# Power_Supply.net
KiCad netlist of a schematic drawn in Altium Designer
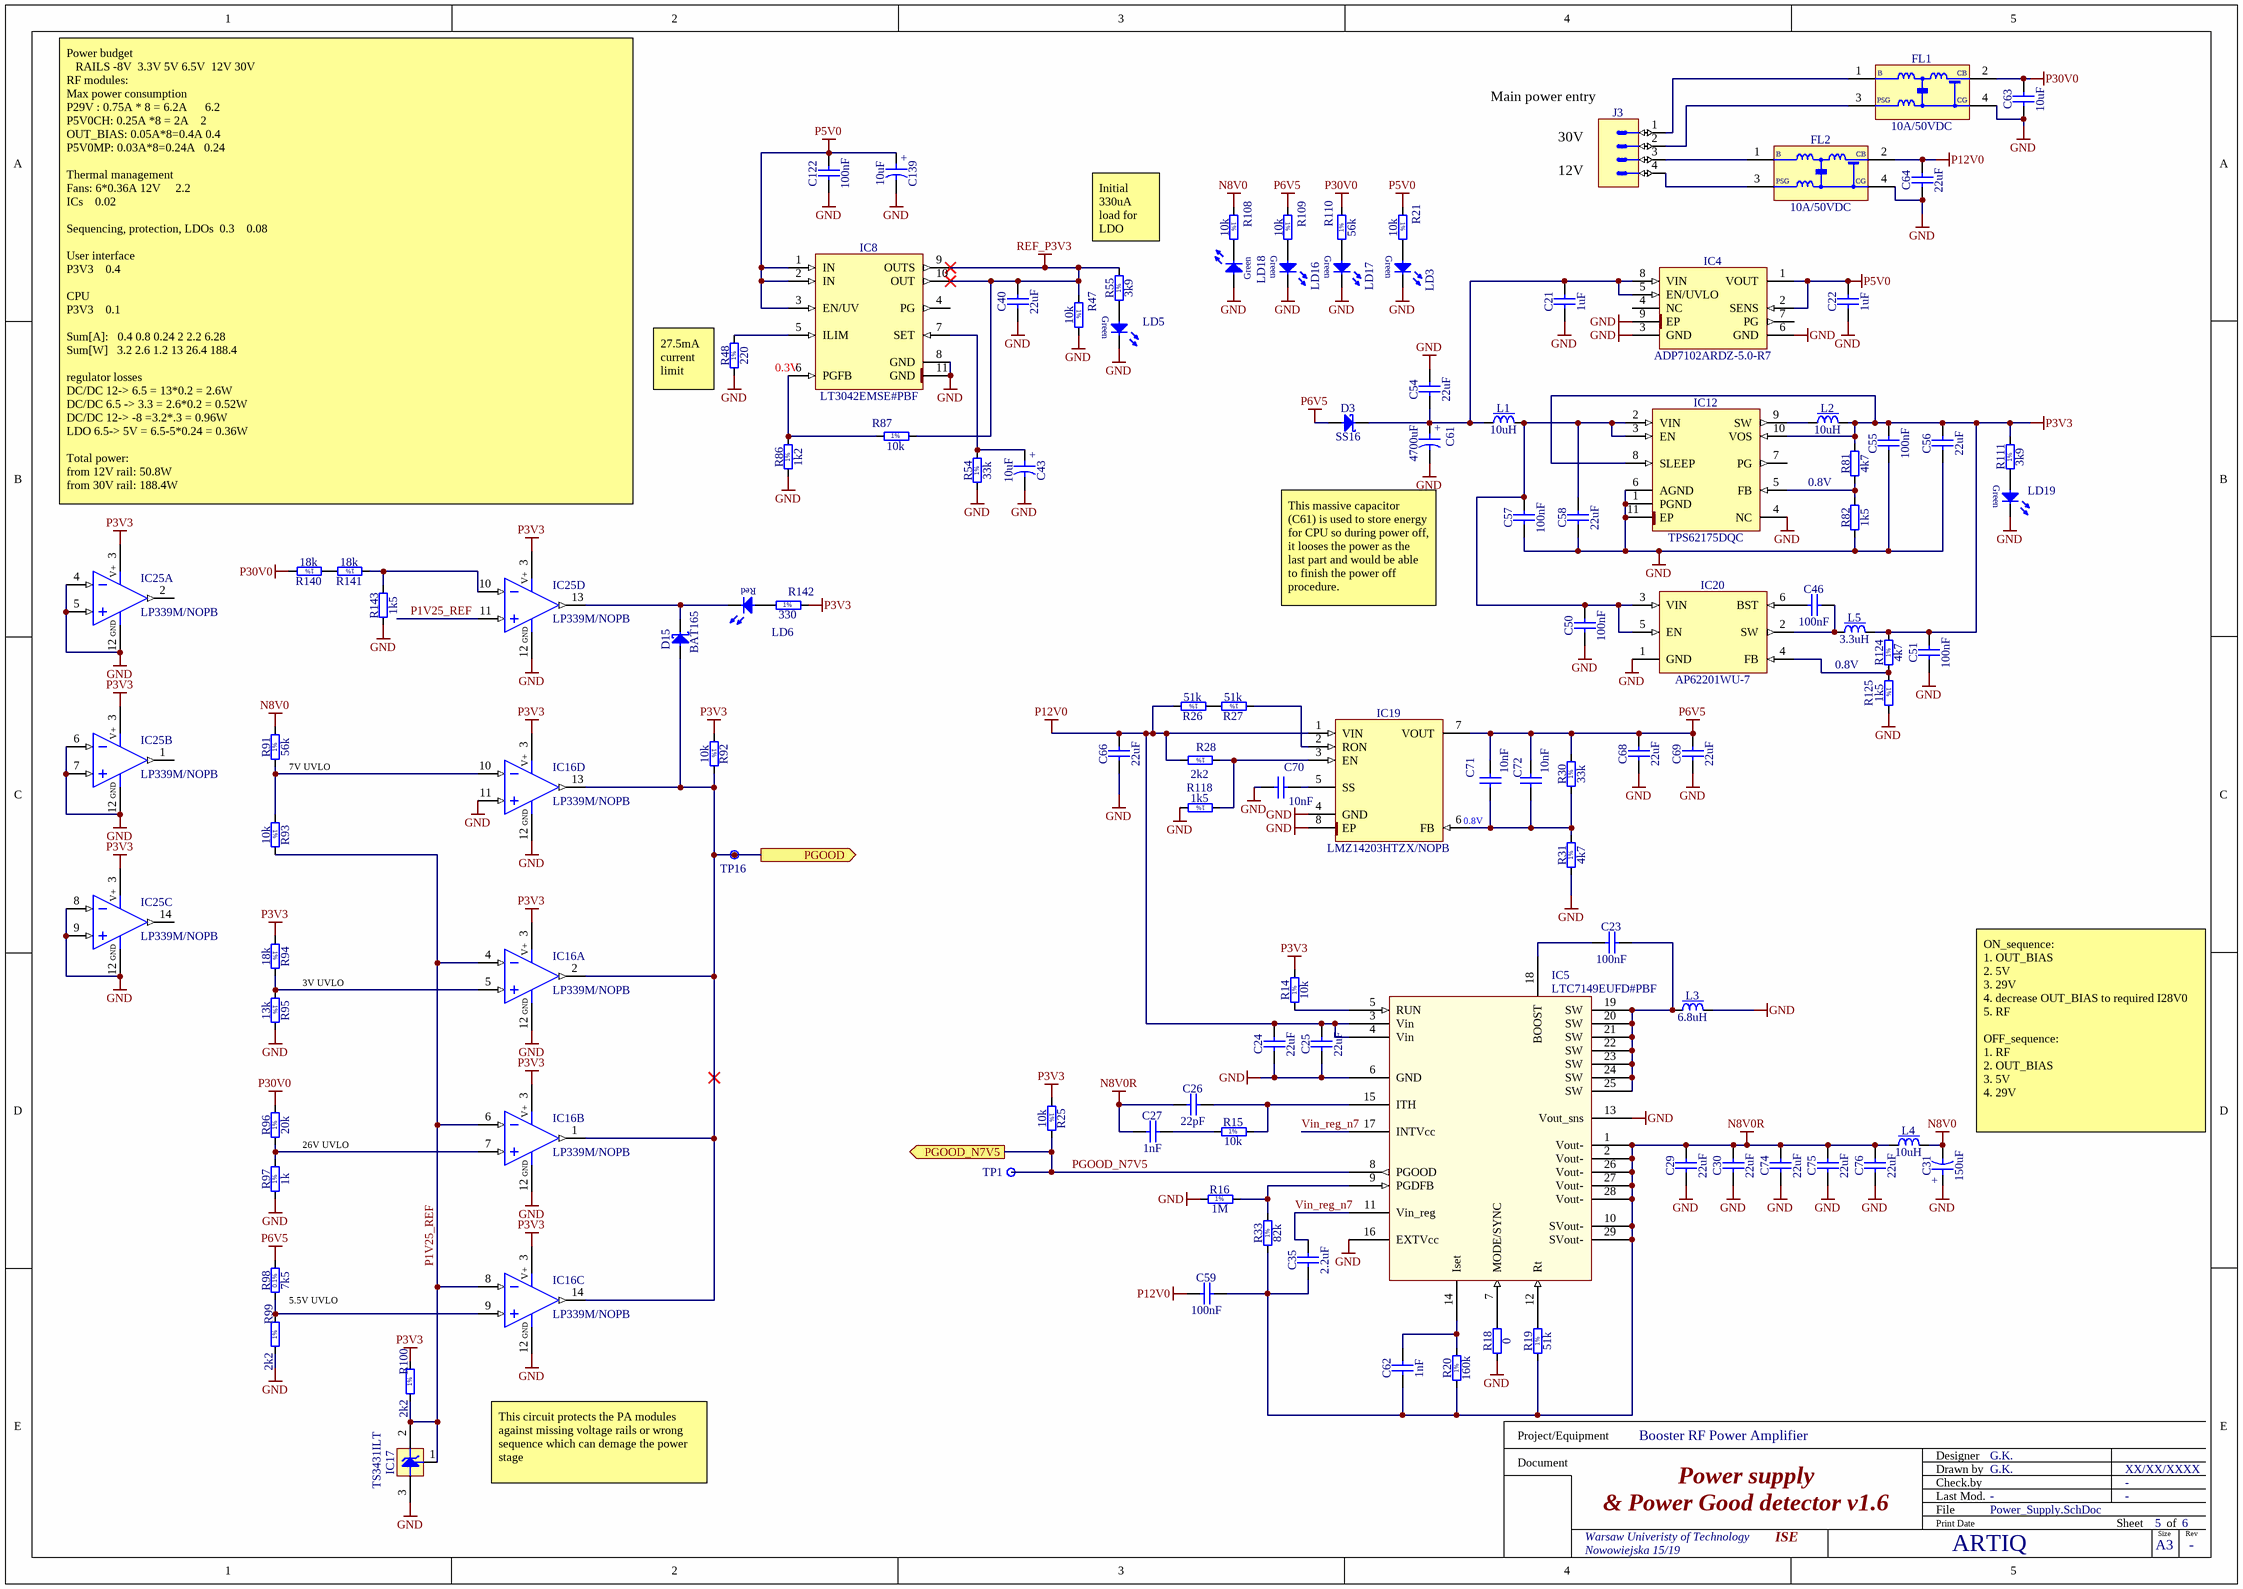
[diagram p0: Power_Supply.SchDoc]

(export (version "E")
  (design (tool "Eeschema 10.0.6"))
  (components
    (comp (ref "C21")
      (value "1uF")
      (footprint "CAPC2012X110N")
      (description "Non-polarised capacitor")
      (fields
        (field (name "PART NUMBER") "CC0805_1UF_50V_10%_X7R")
        (field (name "VOLTAGE") "50V")
        (field (name "AUTHOR") "CERN DEM JLC")
      )
      (libsource (lib "Capacitors") (part "Capacitor - non polarized"))
    )
    (comp (ref "C22")
      (value "1uF")
      (footprint "CAPC2012X110N")
      (description "Non-polarised capacitor")
      (fields
        (field (name "PART NUMBER") "CC0805_1UF_50V_10%_X7R")
        (field (name "VOLTAGE") "50V")
        (field (name "AUTHOR") "CERN DEM JLC")
      )
      (libsource (lib "Capacitors") (part "Capacitor - non polarized"))
    )
    (comp (ref "C23")
      (value "100nF")
      (footprint "CAPC1005X55N")
      (description "Non-polarised capacitor")
      (fields
        (field (name "PART NUMBER") "CC0402_100NF_50V_10%_X7R")
        (field (name "VOLTAGE") "50V")
        (field (name "AUTHOR") "CERN DEM MR")
      )
      (libsource (lib "Capacitors") (part "Capacitor - non polarized"))
    )
    (comp (ref "C24")
      (value "22uF")
      (footprint "CAPC2012X135N")
      (description "Non-polarised capacitor")
      (fields
        (field (name "PART NUMBER") "CC0805_22UF_16V_10%_X5R")
        (field (name "VOLTAGE") "16V")
        (field (name "AUTHOR") "CERN DEM JLC")
      )
      (libsource (lib "Capacitors") (part "Capacitor - non polarized"))
    )
    (comp (ref "C25")
      (value "22uF")
      (footprint "CAPC2012X135N")
      (description "Non-polarised capacitor")
      (fields
        (field (name "PART NUMBER") "CC0805_22UF_16V_10%_X5R")
        (field (name "VOLTAGE") "16V")
        (field (name "AUTHOR") "CERN DEM JLC")
      )
      (libsource (lib "Capacitors") (part "Capacitor - non polarized"))
    )
    (comp (ref "C26")
      (value "22pF")
      (footprint "CAPC1005X55N")
      (description "Non-polarised capacitor")
      (fields
        (field (name "PART NUMBER") "CC0402_22PF_50V_5%_C0G")
        (field (name "VOLTAGE") "50V")
        (field (name "AUTHOR") "CERN DEM JLC")
      )
      (libsource (lib "Capacitors") (part "Capacitor - non polarized"))
    )
    (comp (ref "C27")
      (value "1nF")
      (footprint "CAPC1608X87N")
      (description "Non-polarised capacitor")
      (fields
        (field (name "PART NUMBER") "CC0603_1NF_50V_10%_X7R")
        (field (name "VOLTAGE") "50V")
        (field (name "AUTHOR") "CERN DEM JLC")
      )
      (libsource (lib "Capacitors") (part "Capacitor - non polarized"))
    )
    (comp (ref "C29")
      (value "22uF")
      (footprint "CAPC2012X135N")
      (description "Non-polarised capacitor")
      (fields
        (field (name "PART NUMBER") "CC0805_22UF_16V_10%_X5R")
        (field (name "VOLTAGE") "16V")
        (field (name "AUTHOR") "CERN DEM JLC")
      )
      (libsource (lib "Capacitors") (part "Capacitor - non polarized"))
    )
    (comp (ref "C30")
      (value "22uF")
      (footprint "CAPC2012X135N")
      (description "Non-polarised capacitor")
      (fields
        (field (name "PART NUMBER") "CC0805_22UF_16V_10%_X5R")
        (field (name "VOLTAGE") "16V")
        (field (name "AUTHOR") "CERN DEM JLC")
      )
      (libsource (lib "Capacitors") (part "Capacitor - non polarized"))
    )
    (comp (ref "C31")
      (value "150uF")
      (footprint "CAPMP7343X310N")
      (description "Polarised capacitor")
      (fields
        (field (name "PART NUMBER") "CTE7343-31_150UF_16V_10%_LESR0100")
        (field (name "VOLTAGE") "16V")
        (field (name "AUTHOR") "CERN DEM JLC")
      )
      (libsource (lib "Capacitors") (part "Capacitor - polarized"))
    )
    (comp (ref "C35")
      (value "2.2uF")
      (footprint "CAPC1608X90N")
      (description "Non-polarised capacitor")
      (fields
        (field (name "PART NUMBER") "CC0603_2.2UF_10V_20%_X7R")
        (field (name "VOLTAGE") "10V")
        (field (name "AUTHOR") "CERN DEM JLC")
      )
      (libsource (lib "Capacitors") (part "Capacitor - non polarized"))
    )
    (comp (ref "C40")
      (value "22uF")
      (footprint "CAPC2012X135N")
      (description "Non-polarised capacitor")
      (fields
        (field (name "PART NUMBER") "CC0805_22UF_16V_10%_X5R")
        (field (name "VOLTAGE") "16V")
        (field (name "AUTHOR") "CERN DEM JLC")
      )
      (libsource (lib "Capacitors") (part "Capacitor - non polarized"))
    )
    (comp (ref "C43")
      (value "10uF")
      (footprint "CAPAE430X540N")
      (description "Polarised capacitor")
      (fields
        (field (name "PART NUMBER") "CAE430-540_10UF_16V_20%")
        (field (name "VOLTAGE") "16V")
        (field (name "AUTHOR") "CERN DEM JLC")
      )
      (libsource (lib "Capacitors") (part "Capacitor - polarized"))
    )
    (comp (ref "C46")
      (value "100nF")
      (footprint "CAPC1005X55N")
      (description "Non-polarised capacitor")
      (fields
        (field (name "PART NUMBER") "CC0402_100NF_16V_10%_X7R")
        (field (name "VOLTAGE") "16V")
        (field (name "AUTHOR") "CERN DEM JLC")
      )
      (libsource (lib "Capacitors") (part "Capacitor - non polarized"))
    )
    (comp (ref "C50")
      (value "100nF")
      (footprint "CAPC1005X55N")
      (description "Non-polarised capacitor")
      (fields
        (field (name "PART NUMBER") "CC0402_100NF_16V_10%_X7R")
        (field (name "VOLTAGE") "16V")
        (field (name "AUTHOR") "CERN DEM JLC")
      )
      (libsource (lib "Capacitors") (part "Capacitor - non polarized"))
    )
    (comp (ref "C51")
      (value "100nF")
      (footprint "CAPC1005X55N")
      (description "Non-polarised capacitor")
      (fields
        (field (name "PART NUMBER") "CC0402_100NF_16V_10%_X5R")
        (field (name "VOLTAGE") "16V")
        (field (name "AUTHOR") "CERN DEM JLC")
      )
      (libsource (lib "Capacitors") (part "Capacitor - non polarized"))
    )
    (comp (ref "C54")
      (value "22uF")
      (footprint "CAPC2012X135N")
      (description "Non-polarised capacitor")
      (fields
        (field (name "PART NUMBER") "CC0805_22UF_16V_10%_X5R")
        (field (name "VOLTAGE") "16V")
        (field (name "AUTHOR") "CERN DEM JLC")
      )
      (libsource (lib "Capacitors") (part "Capacitor - non polarized"))
    )
    (comp (ref "C55")
      (value "100nF")
      (footprint "CAPC1005X55N")
      (description "Non-polarised capacitor")
      (fields
        (field (name "PART NUMBER") "CC0402_100NF_16V_10%_X7R")
        (field (name "VOLTAGE") "16V")
        (field (name "AUTHOR") "CERN DEM JLC")
      )
      (libsource (lib "Capacitors") (part "Capacitor - non polarized"))
    )
    (comp (ref "C56")
      (value "22uF")
      (footprint "CAPC2012X135N")
      (description "Non-polarised capacitor")
      (fields
        (field (name "PART NUMBER") "CC0805_22UF_16V_10%_X5R")
        (field (name "VOLTAGE") "16V")
        (field (name "AUTHOR") "CERN DEM JLC")
      )
      (libsource (lib "Capacitors") (part "Capacitor - non polarized"))
    )
    (comp (ref "C57")
      (value "100nF")
      (footprint "CAPC1005X55N")
      (description "Non-polarised capacitor")
      (fields
        (field (name "PART NUMBER") "CC0402_100NF_16V_10%_X7R")
        (field (name "VOLTAGE") "16V")
        (field (name "AUTHOR") "CERN DEM JLC")
      )
      (libsource (lib "Capacitors") (part "Capacitor - non polarized"))
    )
    (comp (ref "C58")
      (value "22uF")
      (footprint "CAPC2012X135N")
      (description "Non-polarised capacitor")
      (fields
        (field (name "PART NUMBER") "CC0805_22UF_16V_10%_X5R")
        (field (name "VOLTAGE") "16V")
        (field (name "AUTHOR") "CERN DEM JLC")
      )
      (libsource (lib "Capacitors") (part "Capacitor - non polarized"))
    )
    (comp (ref "C59")
      (value "100nF")
      (footprint "CAPC1005X55N")
      (description "Non-polarised capacitor")
      (fields
        (field (name "PART NUMBER") "CC0402_100NF_50V_10%_X7R")
        (field (name "VOLTAGE") "50V")
        (field (name "AUTHOR") "CERN DEM MR")
      )
      (libsource (lib "Capacitors") (part "Capacitor - non polarized"))
    )
    (comp (ref "C61")
      (value "4700uF")
      (footprint "CAPAE1900X1680N")
      (description "Polarised capacitor")
      (fields
        (field (name "PART NUMBER") "CAE1900-1680_4700UF_16V_20%")
        (field (name "VOLTAGE") "16V")
        (field (name "AUTHOR") "CERN DEM JLC")
      )
      (libsource (lib "Capacitors") (part "Capacitor - polarized"))
    )
    (comp (ref "C62")
      (value "1nF")
      (footprint "CAPC1608X87N")
      (description "Non-polarised capacitor")
      (fields
        (field (name "PART NUMBER") "CC0603_1NF_50V_10%_X7R")
        (field (name "VOLTAGE") "50V")
        (field (name "AUTHOR") "CERN DEM JLC")
      )
      (libsource (lib "Capacitors") (part "Capacitor - non polarized"))
    )
    (comp (ref "C63")
      (value "10uF")
      (footprint "CAPC3216X190N")
      (description "Non-polarised capacitor")
      (fields
        (field (name "PART NUMBER") "CC1206_10UF_50V_10%_X5R_TDK_CGA5L3X5R1H106K160AB")
        (field (name "VOLTAGE") "50V")
        (field (name "AUTHOR") "CERN DEM BC")
      )
      (libsource (lib "Capacitors") (part "Capacitor - non polarized"))
    )
    (comp (ref "C64")
      (value "22uF")
      (footprint "CAPC2012X135N")
      (description "Non-polarised capacitor")
      (fields
        (field (name "PART NUMBER") "CC0805_22UF_16V_10%_X5R")
        (field (name "VOLTAGE") "16V")
        (field (name "AUTHOR") "CERN DEM JLC")
      )
      (libsource (lib "Capacitors") (part "Capacitor - non polarized"))
    )
    (comp (ref "C66")
      (value "22uF")
      (footprint "CAPC2012X135N")
      (description "Non-polarised capacitor")
      (fields
        (field (name "PART NUMBER") "CC0805_22UF_16V_10%_X5R")
        (field (name "VOLTAGE") "16V")
        (field (name "AUTHOR") "CERN DEM JLC")
      )
      (libsource (lib "Capacitors") (part "Capacitor - non polarized"))
    )
    (comp (ref "C68")
      (value "22uF")
      (footprint "CAPC2012X135N")
      (description "Non-polarised capacitor")
      (fields
        (field (name "PART NUMBER") "CC0805_22UF_16V_10%_X5R")
        (field (name "VOLTAGE") "16V")
        (field (name "AUTHOR") "CERN DEM JLC")
      )
      (libsource (lib "Capacitors") (part "Capacitor - non polarized"))
    )
    (comp (ref "C69")
      (value "22uF")
      (footprint "CAPC2012X135N")
      (description "Non-polarised capacitor")
      (fields
        (field (name "PART NUMBER") "CC0805_22UF_16V_10%_X5R")
        (field (name "VOLTAGE") "16V")
        (field (name "AUTHOR") "CERN DEM JLC")
      )
      (libsource (lib "Capacitors") (part "Capacitor - non polarized"))
    )
    (comp (ref "C70")
      (value "10nF")
      (footprint "CAPC1608X87N")
      (description "Non-polarised capacitor")
      (fields
        (field (name "PART NUMBER") "CC0603_10NF_50V_5%_C0G")
        (field (name "VOLTAGE") "50V")
        (field (name "AUTHOR") "CERN DEM JLC")
      )
      (libsource (lib "Capacitors") (part "Capacitor - non polarized"))
    )
    (comp (ref "C71")
      (value "10nF")
      (footprint "CAPC1608X87N")
      (description "Non-polarised capacitor")
      (fields
        (field (name "PART NUMBER") "CC0603_10NF_50V_5%_C0G")
        (field (name "VOLTAGE") "50V")
        (field (name "AUTHOR") "CERN DEM JLC")
      )
      (libsource (lib "Capacitors") (part "Capacitor - non polarized"))
    )
    (comp (ref "C72")
      (value "10nF")
      (footprint "CAPC1608X87N")
      (description "Non-polarised capacitor")
      (fields
        (field (name "PART NUMBER") "CC0603_10NF_50V_5%_C0G")
        (field (name "VOLTAGE") "50V")
        (field (name "AUTHOR") "CERN DEM JLC")
      )
      (libsource (lib "Capacitors") (part "Capacitor - non polarized"))
    )
    (comp (ref "C74")
      (value "22uF")
      (footprint "CAPC2012X135N")
      (description "Non-polarised capacitor")
      (fields
        (field (name "PART NUMBER") "CC0805_22UF_16V_10%_X5R")
        (field (name "VOLTAGE") "16V")
        (field (name "AUTHOR") "CERN DEM JLC")
      )
      (libsource (lib "Capacitors") (part "Capacitor - non polarized"))
    )
    (comp (ref "C75")
      (value "22uF")
      (footprint "CAPC2012X135N")
      (description "Non-polarised capacitor")
      (fields
        (field (name "PART NUMBER") "CC0805_22UF_16V_10%_X5R")
        (field (name "VOLTAGE") "16V")
        (field (name "AUTHOR") "CERN DEM JLC")
      )
      (libsource (lib "Capacitors") (part "Capacitor - non polarized"))
    )
    (comp (ref "C76")
      (value "22uF")
      (footprint "CAPC2012X135N")
      (description "Non-polarised capacitor")
      (fields
        (field (name "PART NUMBER") "CC0805_22UF_16V_10%_X5R")
        (field (name "VOLTAGE") "16V")
        (field (name "AUTHOR") "CERN DEM JLC")
      )
      (libsource (lib "Capacitors") (part "Capacitor - non polarized"))
    )
    (comp (ref "C122")
      (value "100nF")
      (footprint "CAPC1005X55N")
      (description "Non-polarised capacitor")
      (fields
        (field (name "PART NUMBER") "CC0402_100NF_16V_10%_X7R")
        (field (name "VOLTAGE") "16V")
        (field (name "AUTHOR") "CERN DEM JLC")
      )
      (libsource (lib "Capacitors") (part "Capacitor - non polarized"))
    )
    (comp (ref "C139")
      (value "10uF")
      (footprint "CAPAE430X540N")
      (description "Polarised capacitor")
      (fields
        (field (name "PART NUMBER") "CAE430-540_10UF_16V_20%")
        (field (name "VOLTAGE") "16V")
        (field (name "AUTHOR") "CERN DEM JLC")
      )
      (libsource (lib "Capacitors") (part "Capacitor - polarized"))
    )
    (comp (ref "D3")
      (value "SS16")
      (footprint "DIOM5127X229N")
      (description "Schottky Diode")
      (fields
        (field (name "VOLTAGE") "60V")
        (field (name "POWER") "1A")
        (field (name "AUTHOR") "CERN DEM JLC")
      )
      (libsource (lib "ICs And Semiconductors") (part "Diode Schottky"))
    )
    (comp (ref "D15")
      (value "BAT165")
      (footprint "SOD2512X110N")
      (description "Schottky Diode")
      (fields
        (field (name "VOLTAGE") "40V")
        (field (name "POWER") "750mA")
        (field (name "AUTHOR") "CERN DEM JLC")
      )
      (libsource (lib "ICs And Semiconductors") (part "Diode Schottky"))
    )
    (comp (ref "FL1")
      (value "10A/50VDC")
      (footprint "FIL_MURATA_BNX02")
      (description "Block Type EMIFIL (LC Combined)")
      (fields
        (field (name "PART NUMBER") "FIL_MURATA_BNX022-01L")
        (field (name "MANUFACTURER") "MURATA")
        (field (name "AUTHOR") "CERN DEM JLC")
      )
      (libsource (lib "Inductors & Transformers") (part "FIL_MURATA_BNX02"))
    )
    (comp (ref "FL2")
      (value "10A/50VDC")
      (footprint "FIL_MURATA_BNX02")
      (description "Block Type EMIFIL (LC Combined)")
      (fields
        (field (name "PART NUMBER") "FIL_MURATA_BNX022-01L")
        (field (name "MANUFACTURER") "MURATA")
        (field (name "AUTHOR") "CERN DEM JLC")
      )
      (libsource (lib "Inductors & Transformers") (part "FIL_MURATA_BNX02"))
    )
    (comp (ref "IC4")
      (value "ADP7102ARDZ-5.0-R7")
      (footprint "SOIC127P600X175-9N-R241X309")
      (description "300 mA, Low Noise, CMOS LDO Linear Regulator")
      (fields (field (name "MANUFACTURER") "ANALOG DEVICES") (field (name "AUTHOR") "CERN DEM JLC"))
      (libsource (lib "ICs And Semiconductors") (part "ADP7102ARDZ-X.X-R7"))
    )
    (comp (ref "IC5")
      (value "LTC7149EUFD#PBF")
      (footprint "QFN50P400X500X80_HS-29N")
      (description "LTC7149 - 60V, 4A Synchronous Step-Down Regulator for Inverting Outputs")
      (fields (field (name "MANUFACTURER") "Linear technology"))
      (libsource (lib "misc") (part "LTC7149EUFD#PBF"))
    )
    (comp (ref "IC8")
      (value "LT3042EMSE#PBF")
      (footprint "SOP50P490X110-11N-R168X198")
      (description "20V, 200mA, Ultralow Noise, Ultrahigh PSRR RF Linear Regulator")
      (fields (field (name "MANUFACTURER") "LINEAR TECHNOLOGY") (field (name "AUTHOR") "CERN DEM MR"))
      (libsource (lib "ICs And Semiconductors") (part "LT3042"))
    )
    (comp (ref "IC12")
      (value "TPS62175DQC")
      (footprint "SON50P200X300X80-11N-R94X250")
      (description "4.75-28VDC to 1-6VDC, 500mA Step-Down Converter With Sleep Mode")
      (fields (field (name "MANUFACTURER") "TEXAS INSTRUMENTS") (field (name "AUTHOR") "CERN DEM JMW"))
      (libsource (lib "ICs And Semiconductors") (part "TPS62175"))
    )
    (comp (ref "IC16")
      (value "LP339M/NOPB")
      (footprint "SOIC127P600X175-14N")
      (description "Quad Operational Amplifier")
      (fields (field (name "MANUFACTURER") "TEXAS INSTRUMENTS") (field (name "AUTHOR") "CERN DEM MR"))
      (libsource (lib "ICs And Semiconductors") (part "Operational Amplifier x4 Type5"))
    )
    (comp (ref "IC17")
      (value "TS3431ILT")
      (footprint "SOT95P237X112-3N")
      (description "Precision Reference 1=Adj 2=Cathode 3=Anode")
      (fields (field (name "MANUFACTURER") "ST MICROELECTRONICS") (field (name "AUTHOR") "CERN DEM JLC"))
      (libsource (lib "ICs And Semiconductors") (part "VREF 1ADJ-2C-3A"))
    )
    (comp (ref "IC19")
      (value "LMZ14203HTZX/NOPB")
      (footprint "TEXAS_TO-PMOD (NDW)")
      (description "3A SIMPLE SWITCHER® Power Module with 42V Maximum Input Voltage")
      (fields (field (name "MANUFACTURER") "TEXAS INSTRUMENTS") (field (name "AUTHOR") "GK"))
      (libsource (lib "LIBRARY_SCH") (part "PM_LMZ14203"))
    )
    (comp (ref "IC20")
      (value "AP62201WU-7")
      (footprint "SOT95P280X100-6N")
      (description "4.2V TO 18V INPUT, 2A LOW IQ SYNCHRONOUS BUCK CONVERTER")
      (fields (field (name "MANUFACTURER") "DIODES INCORPORATED") (field (name "AUTHOR") "CERN DEM HF"))
      (libsource (lib "ICs And Semiconductors") (part "AP62201WU"))
    )
    (comp (ref "IC25")
      (value "LP339M/NOPB")
      (footprint "SOIC127P600X175-14N")
      (description "Quad Operational Amplifier")
      (fields (field (name "MANUFACTURER") "TEXAS INSTRUMENTS") (field (name "AUTHOR") "CERN DEM MR"))
      (libsource (lib "ICs And Semiconductors") (part "Operational Amplifier x4 Type5"))
    )
    (comp (ref "J3")
      (value "~")
      (footprint "PHOENIX_1755752")
      (description "Connector 4 Male")
      (fields
        (field (name "PART NUMBER") "PHOENIX_1755752")
        (field (name "MANUFACTURER") "PHOENIX CONTACT")
        (field (name "AUTHOR") "CERN DEM JLC")
      )
      (libsource (lib "Connectors") (part "Connector 4 Male"))
    )
    (comp (ref "L1")
      (value "10uH")
      (footprint "IND_MURATA-PS_8400")
      (description "Inductor With Core")
      (fields
        (field (name "PART NUMBER") "IND_10UH_10%_MURATA-PS_8400")
        (field (name "POWER") "950mA")
        (field (name "AUTHOR") "CERN DEM JLC")
      )
      (libsource (lib "Inductors & Transformers") (part "Inductor With Magnetic core"))
    )
    (comp (ref "L2")
      (value "10uH")
      (footprint "IND_MURATA-PS_8400")
      (description "Inductor With Core")
      (fields
        (field (name "PART NUMBER") "IND_10UH_10%_MURATA-PS_8400")
        (field (name "POWER") "950mA")
        (field (name "AUTHOR") "CERN DEM JLC")
      )
      (libsource (lib "Inductors & Transformers") (part "Inductor With Magnetic core"))
    )
    (comp (ref "L3")
      (value "6.8uH")
      (footprint "INDM6965X300N")
      (description "Inductor With Core")
      (fields
        (field (name "PART NUMBER") "IND2525_6.8UH_20%_VISHAY_IHLP-2525CZ")
        (field (name "POWER") "9A")
        (field (name "AUTHOR") "CERN DEM JLC")
      )
      (libsource (lib "Inductors & Transformers") (part "Inductor With Magnetic core"))
    )
    (comp (ref "L4")
      (value "10uH")
      (footprint "IND_MURATA-PS_8400")
      (description "Inductor With Core")
      (fields
        (field (name "PART NUMBER") "IND_10UH_10%_MURATA-PS_8400")
        (field (name "POWER") "950mA")
        (field (name "AUTHOR") "CERN DEM JLC")
      )
      (libsource (lib "Inductors & Transformers") (part "Inductor With Magnetic core"))
    )
    (comp (ref "L5")
      (value "3.3uH")
      (footprint "IND_WURTH_WE-TPC_4828")
      (description "Inductor With Core")
      (fields
        (field (name "PART NUMBER") "IND_3.3UH_30%_WURTH_WE-TPC_744043003")
        (field (name "POWER") "2.15A")
        (field (name "AUTHOR") "CERN DEM JLC")
      )
      (libsource (lib "Inductors & Transformers") (part "Inductor With Magnetic core"))
    )
    (comp (ref "LD3")
      (value "Green")
      (footprint "LED_KINGBRIGHT_KPH-1608CGCK")
      (description "LED Green 1C 2A")
      (fields
        (field (name "PART NUMBER") "LED_KINGBRIGHT_KPH-1608CGCK")
        (field (name "MANUFACTURER") "KINGBRIGHT")
        (field (name "AUTHOR") "CERN DEM JLC")
      )
      (libsource (lib "ICs And Semiconductors") (part "LED Green 1C 2A"))
    )
    (comp (ref "LD5")
      (value "Green")
      (footprint "LED_OSRAM_LGL29K")
      (description "LED Green 1C 2A")
      (fields
        (field (name "PART NUMBER") "LED_OSRAM_LG L29K-G2J1-24-Z")
        (field (name "MANUFACTURER") "OSRAM")
        (field (name "AUTHOR") "CERN DEM JLC")
      )
      (libsource (lib "ICs And Semiconductors") (part "LED Green 1C 2A"))
    )
    (comp (ref "LD6")
      (value "Hyper Red")
      (footprint "LED_KINGBRIGHT_KPH-1608SURCK")
      (description "LED Red 1C 2A")
      (fields
        (field (name "PART NUMBER") "LED_KINGBRIGHT_KPH-1608SURCK")
        (field (name "MANUFACTURER") "KINGBRIGHT")
        (field (name "AUTHOR") "CERN DEM JLC")
      )
      (libsource (lib "ICs And Semiconductors") (part "LED Red 1C 2A"))
    )
    (comp (ref "LD16")
      (value "Green")
      (footprint "LED_KINGBRIGHT_KPH-1608CGCK")
      (description "LED Green 1C 2A")
      (fields
        (field (name "PART NUMBER") "LED_KINGBRIGHT_KPH-1608CGCK")
        (field (name "MANUFACTURER") "KINGBRIGHT")
        (field (name "AUTHOR") "CERN DEM JLC")
      )
      (libsource (lib "ICs And Semiconductors") (part "LED Green 1C 2A"))
    )
    (comp (ref "LD17")
      (value "Green")
      (footprint "LED_KINGBRIGHT_KPH-1608CGCK")
      (description "LED Green 1C 2A")
      (fields
        (field (name "PART NUMBER") "LED_KINGBRIGHT_KPH-1608CGCK")
        (field (name "MANUFACTURER") "KINGBRIGHT")
        (field (name "AUTHOR") "CERN DEM JLC")
      )
      (libsource (lib "ICs And Semiconductors") (part "LED Green 1C 2A"))
    )
    (comp (ref "LD18")
      (value "Green")
      (footprint "LED_KINGBRIGHT_KPH-1608CGCK")
      (description "LED Green 1C 2A")
      (fields
        (field (name "PART NUMBER") "LED_KINGBRIGHT_KPH-1608CGCK")
        (field (name "MANUFACTURER") "KINGBRIGHT")
        (field (name "AUTHOR") "CERN DEM JLC")
      )
      (libsource (lib "ICs And Semiconductors") (part "LED Green 1C 2A"))
    )
    (comp (ref "LD19")
      (value "Green")
      (footprint "LED_OSRAM_LGL29K")
      (description "LED Green 1C 2A")
      (fields
        (field (name "PART NUMBER") "LED_OSRAM_LG L29K-G2J1-24-Z")
        (field (name "MANUFACTURER") "OSRAM")
        (field (name "AUTHOR") "CERN DEM JLC")
      )
      (libsource (lib "ICs And Semiconductors") (part "LED Green 1C 2A"))
    )
    (comp (ref "R14")
      (value "10k")
      (footprint "RESC1005X40N")
      (description "Resistor - 1%")
      (fields
        (field (name "PART NUMBER") "R0402_10K_1%_0.0625W_100PPM")
        (field (name "POWER") "0.0625W")
        (field (name "AUTHOR") "CERN DEM JLC")
      )
      (libsource (lib "Resistors") (part "Resistor - 1%"))
    )
    (comp (ref "R15")
      (value "10k")
      (footprint "RESC1005X40N")
      (description "Resistor - 1%")
      (fields
        (field (name "PART NUMBER") "R0402_10K_1%_0.0625W_100PPM")
        (field (name "POWER") "0.0625W")
        (field (name "AUTHOR") "CERN DEM JLC")
      )
      (libsource (lib "Resistors") (part "Resistor - 1%"))
    )
    (comp (ref "R16")
      (value "1M")
      (footprint "RESC1005X40N")
      (description "Resistor - 1%")
      (fields
        (field (name "PART NUMBER") "R0402_1M_1%_0.0625W_100PPM")
        (field (name "POWER") "0.0625W")
        (field (name "AUTHOR") "CERN DEM JLC")
      )
      (libsource (lib "Resistors") (part "Resistor - 1%"))
    )
    (comp (ref "R18")
      (value "0")
      (footprint "RESC1005X40N")
      (description "Resistor")
      (fields
        (field (name "PART NUMBER") "R0402_0R_JUMPER")
        (field (name "MANUFACTURER") "GENERIC")
        (field (name "AUTHOR") "CERN DEM JLC")
      )
      (libsource (lib "Resistors") (part "Resistor"))
    )
    (comp (ref "R19")
      (value "51k")
      (footprint "RESC1005X40N")
      (description "Resistor - 1%")
      (fields
        (field (name "PART NUMBER") "R0402_51K_1%_0.0625W_100PPM")
        (field (name "POWER") "0.0625W")
        (field (name "AUTHOR") "CERN DEM JLC")
      )
      (libsource (lib "Resistors") (part "Resistor - 1%"))
    )
    (comp (ref "R20")
      (value "160k")
      (footprint "RESC1005X40N")
      (description "Resistor - 1%")
      (fields
        (field (name "PART NUMBER") "R0402_160K_1%_0.0625W_100PPM")
        (field (name "POWER") "0.0625W")
        (field (name "AUTHOR") "CERN DEM JLC")
      )
      (libsource (lib "Resistors") (part "Resistor - 1%"))
    )
    (comp (ref "R21")
      (value "10k")
      (footprint "RESC1005X40N")
      (description "Resistor - 1%")
      (fields
        (field (name "PART NUMBER") "R0402_10K_1%_0.0625W_100PPM")
        (field (name "POWER") "0.0625W")
        (field (name "AUTHOR") "CERN DEM JLC")
      )
      (libsource (lib "Resistors") (part "Resistor - 1%"))
    )
    (comp (ref "R25")
      (value "10k")
      (footprint "RESC1005X40N")
      (description "Resistor - 1%")
      (fields
        (field (name "PART NUMBER") "R0402_10K_1%_0.0625W_100PPM")
        (field (name "POWER") "0.0625W")
        (field (name "AUTHOR") "CERN DEM JLC")
      )
      (libsource (lib "Resistors") (part "Resistor - 1%"))
    )
    (comp (ref "R26")
      (value "51k")
      (footprint "RESC1005X40N")
      (description "Resistor - 1%")
      (fields
        (field (name "PART NUMBER") "R0402_51K_1%_0.0625W_100PPM")
        (field (name "POWER") "0.0625W")
        (field (name "AUTHOR") "CERN DEM JLC")
      )
      (libsource (lib "Resistors") (part "Resistor - 1%"))
    )
    (comp (ref "R27")
      (value "51k")
      (footprint "RESC1005X40N")
      (description "Resistor - 1%")
      (fields
        (field (name "PART NUMBER") "R0402_51K_1%_0.0625W_100PPM")
        (field (name "POWER") "0.0625W")
        (field (name "AUTHOR") "CERN DEM JLC")
      )
      (libsource (lib "Resistors") (part "Resistor - 1%"))
    )
    (comp (ref "R28")
      (value "2k2")
      (footprint "RESC1005X40N")
      (description "Resistor - 1%")
      (fields
        (field (name "PART NUMBER") "R0402_2K2_1%_0.0625W_100PPM")
        (field (name "POWER") "0.0625W")
        (field (name "AUTHOR") "CERN DEM JLC")
      )
      (libsource (lib "Resistors") (part "Resistor - 1%"))
    )
    (comp (ref "R30")
      (value "33k")
      (footprint "RESC1608X55N")
      (description "Resistor - 1%")
      (fields
        (field (name "PART NUMBER") "R0603_33K_1%_0.1W_100PPM")
        (field (name "POWER") "0.1W")
        (field (name "AUTHOR") "CERN DEM JLC")
      )
      (libsource (lib "Resistors") (part "Resistor - 1%"))
    )
    (comp (ref "R31")
      (value "4k7")
      (footprint "RESC1608X55N")
      (description "Resistor - 1%")
      (fields
        (field (name "PART NUMBER") "R0603_4K7_1%_0.1W_100PPM")
        (field (name "POWER") "0.1W")
        (field (name "AUTHOR") "CERN DEM JLC")
      )
      (libsource (lib "Resistors") (part "Resistor - 1%"))
    )
    (comp (ref "R33")
      (value "82k")
      (footprint "RESC1608X55N")
      (description "Resistor - 1%")
      (fields
        (field (name "PART NUMBER") "R0603_82K_1%_0.1W_100PPM")
        (field (name "POWER") "0.1W")
        (field (name "AUTHOR") "CERN DEM JLC")
      )
      (libsource (lib "Resistors") (part "Resistor - 1%"))
    )
    (comp (ref "R47")
      (value "10k")
      (footprint "RESC1005X40N")
      (description "Resistor - 1%")
      (fields
        (field (name "PART NUMBER") "R0402_10K_1%_0.0625W_100PPM")
        (field (name "POWER") "0.0625W")
        (field (name "AUTHOR") "CERN DEM JLC")
      )
      (libsource (lib "Resistors") (part "Resistor - 1%"))
    )
    (comp (ref "R48")
      (value "220")
      (footprint "RESC1005X40N")
      (description "Resistor - 1%")
      (fields
        (field (name "PART NUMBER") "R0402_220R_1%_0.0625W_100PPM")
        (field (name "POWER") "0.0625W")
        (field (name "AUTHOR") "CERN DEM JLC")
      )
      (libsource (lib "Resistors") (part "Resistor - 1%"))
    )
    (comp (ref "R54")
      (value "33k")
      (footprint "RESC1608X55N")
      (description "Resistor - 1%")
      (fields
        (field (name "PART NUMBER") "R0603_33K_1%_0.1W_100PPM")
        (field (name "POWER") "0.1W")
        (field (name "AUTHOR") "CERN DEM JLC")
      )
      (libsource (lib "Resistors") (part "Resistor - 1%"))
    )
    (comp (ref "R55")
      (value "3k9")
      (footprint "RESC1005X40N")
      (description "Resistor - 1%")
      (fields
        (field (name "PART NUMBER") "R0402_3K9_1%_0.0625W_100PPM")
        (field (name "POWER") "0.0625W")
        (field (name "AUTHOR") "CERN DEM JLC")
      )
      (libsource (lib "Resistors") (part "Resistor - 1%"))
    )
    (comp (ref "R81")
      (value "4k7")
      (footprint "RESC1608X55N")
      (description "Resistor - 1%")
      (fields
        (field (name "PART NUMBER") "R0603_4K7_1%_0.1W_100PPM")
        (field (name "POWER") "0.1W")
        (field (name "AUTHOR") "CERN DEM JLC")
      )
      (libsource (lib "Resistors") (part "Resistor - 1%"))
    )
    (comp (ref "R82")
      (value "1k5")
      (footprint "RESC1608X55N")
      (description "Resistor - 1%")
      (fields
        (field (name "PART NUMBER") "R0603_1K5_1%_0.1W_100PPM")
        (field (name "POWER") "0.1W")
        (field (name "AUTHOR") "CERN DEM JLC")
      )
      (libsource (lib "Resistors") (part "Resistor - 1%"))
    )
    (comp (ref "R86")
      (value "1k2")
      (footprint "RESC1005X40N")
      (description "Resistor - 1%")
      (fields
        (field (name "PART NUMBER") "R0402_1K2_1%_0.0625W_100PPM")
        (field (name "POWER") "0.0625W")
        (field (name "AUTHOR") "CERN DEM JLC")
      )
      (libsource (lib "Resistors") (part "Resistor - 1%"))
    )
    (comp (ref "R87")
      (value "10k")
      (footprint "RESC1005X40N")
      (description "Resistor - 1%")
      (fields
        (field (name "PART NUMBER") "R0402_10K_1%_0.0625W_100PPM")
        (field (name "POWER") "0.0625W")
        (field (name "AUTHOR") "CERN DEM JLC")
      )
      (libsource (lib "Resistors") (part "Resistor - 1%"))
    )
    (comp (ref "R91")
      (value "56k")
      (footprint "RESC1608X55N")
      (description "Resistor - 1%")
      (fields
        (field (name "PART NUMBER") "R0603_56K_1%_0.1W_100PPM")
        (field (name "POWER") "0.1W")
        (field (name "AUTHOR") "CERN DEM JLC")
      )
      (libsource (lib "Resistors") (part "Resistor - 1%"))
    )
    (comp (ref "R92")
      (value "10k")
      (footprint "RESC1005X40N")
      (description "Resistor - 1%")
      (fields
        (field (name "PART NUMBER") "R0402_10K_1%_0.0625W_100PPM")
        (field (name "POWER") "0.0625W")
        (field (name "AUTHOR") "CERN DEM JLC")
      )
      (libsource (lib "Resistors") (part "Resistor - 1%"))
    )
    (comp (ref "R93")
      (value "10k")
      (footprint "RESC1005X40N")
      (description "Resistor - 1%")
      (fields
        (field (name "PART NUMBER") "R0402_10K_1%_0.0625W_100PPM")
        (field (name "POWER") "0.0625W")
        (field (name "AUTHOR") "CERN DEM JLC")
      )
      (libsource (lib "Resistors") (part "Resistor - 1%"))
    )
    (comp (ref "R94")
      (value "18k")
      (footprint "RESC1608X55N")
      (description "Resistor - 1%")
      (fields
        (field (name "PART NUMBER") "R0603_18K_1%_0.1W_100PPM")
        (field (name "POWER") "0.1W")
        (field (name "AUTHOR") "CERN DEM JLC")
      )
      (libsource (lib "Resistors") (part "Resistor - 1%"))
    )
    (comp (ref "R95")
      (value "13k")
      (footprint "RESC1608X55N")
      (description "Resistor - 1%")
      (fields
        (field (name "PART NUMBER") "R0603_13K_1%_0.1W_100PPM")
        (field (name "POWER") "0.1W")
        (field (name "AUTHOR") "CERN DEM JLC")
      )
      (libsource (lib "Resistors") (part "Resistor - 1%"))
    )
    (comp (ref "R96")
      (value "20k")
      (footprint "RESC1608X55N")
      (description "Resistor - 1%")
      (fields
        (field (name "PART NUMBER") "R0603_20K_1%_0.1W_100PPM")
        (field (name "POWER") "0.1W")
        (field (name "AUTHOR") "CERN DEM JLC")
      )
      (libsource (lib "Resistors") (part "Resistor - 1%"))
    )
    (comp (ref "R97")
      (value "1k")
      (footprint "RESC1608X55N")
      (description "Resistor - 1%")
      (fields
        (field (name "PART NUMBER") "R0603_1K_1%_0.1W_100PPM")
        (field (name "POWER") "0.1W")
        (field (name "AUTHOR") "CERN DEM JLC")
      )
      (libsource (lib "Resistors") (part "Resistor - 1%"))
    )
    (comp (ref "R98")
      (value "7k5")
      (footprint "RESC1608X55N")
      (description "Resistor - 0.1%")
      (fields
        (field (name "PART NUMBER") "R0603_7K5_0.1%_0.063W_10PPM")
        (field (name "POWER") "0.063W")
        (field (name "AUTHOR") "CERN DEM JLC")
      )
      (libsource (lib "Resistors") (part "Resistor - 0.1%"))
    )
    (comp (ref "R99")
      (value "2k2")
      (footprint "RESC1005X40N")
      (description "Resistor - 1%")
      (fields
        (field (name "PART NUMBER") "R0402_2K2_1%_0.0625W_100PPM")
        (field (name "POWER") "0.0625W")
        (field (name "AUTHOR") "CERN DEM JLC")
      )
      (libsource (lib "Resistors") (part "Resistor - 1%"))
    )
    (comp (ref "R100")
      (value "2k2")
      (footprint "RESC1005X40N")
      (description "Resistor - 1%")
      (fields
        (field (name "PART NUMBER") "R0402_2K2_1%_0.0625W_100PPM")
        (field (name "POWER") "0.0625W")
        (field (name "AUTHOR") "CERN DEM JLC")
      )
      (libsource (lib "Resistors") (part "Resistor - 1%"))
    )
    (comp (ref "R108")
      (value "10k")
      (footprint "RESC1005X40N")
      (description "Resistor - 1%")
      (fields
        (field (name "PART NUMBER") "R0402_10K_1%_0.0625W_100PPM")
        (field (name "POWER") "0.0625W")
        (field (name "AUTHOR") "CERN DEM JLC")
      )
      (libsource (lib "Resistors") (part "Resistor - 1%"))
    )
    (comp (ref "R109")
      (value "10k")
      (footprint "RESC1005X40N")
      (description "Resistor - 1%")
      (fields
        (field (name "PART NUMBER") "R0402_10K_1%_0.0625W_100PPM")
        (field (name "POWER") "0.0625W")
        (field (name "AUTHOR") "CERN DEM JLC")
      )
      (libsource (lib "Resistors") (part "Resistor - 1%"))
    )
    (comp (ref "R110")
      (value "56k")
      (footprint "RESC1608X55N")
      (description "Resistor - 1%")
      (fields
        (field (name "PART NUMBER") "R0603_56K_1%_0.1W_100PPM")
        (field (name "POWER") "0.1W")
        (field (name "AUTHOR") "CERN DEM JLC")
      )
      (libsource (lib "Resistors") (part "Resistor - 1%"))
    )
    (comp (ref "R111")
      (value "3k9")
      (footprint "RESC1005X40N")
      (description "Resistor - 1%")
      (fields
        (field (name "PART NUMBER") "R0402_3K9_1%_0.0625W_100PPM")
        (field (name "POWER") "0.0625W")
        (field (name "AUTHOR") "CERN DEM JLC")
      )
      (libsource (lib "Resistors") (part "Resistor - 1%"))
    )
    (comp (ref "R118")
      (value "1k5")
      (footprint "RESC1608X55N")
      (description "Resistor - 1%")
      (fields
        (field (name "PART NUMBER") "R0603_1K5_1%_0.1W_100PPM")
        (field (name "POWER") "0.1W")
        (field (name "AUTHOR") "CERN DEM JLC")
      )
      (libsource (lib "Resistors") (part "Resistor - 1%"))
    )
    (comp (ref "R124")
      (value "4k7")
      (footprint "RESC1608X55N")
      (description "Resistor - 1%")
      (fields
        (field (name "PART NUMBER") "R0603_4K7_1%_0.1W_100PPM")
        (field (name "POWER") "0.1W")
        (field (name "AUTHOR") "CERN DEM JLC")
      )
      (libsource (lib "Resistors") (part "Resistor - 1%"))
    )
    (comp (ref "R125")
      (value "1k5")
      (footprint "RESC1608X55N")
      (description "Resistor - 1%")
      (fields
        (field (name "PART NUMBER") "R0603_1K5_1%_0.1W_100PPM")
        (field (name "POWER") "0.1W")
        (field (name "AUTHOR") "CERN DEM JLC")
      )
      (libsource (lib "Resistors") (part "Resistor - 1%"))
    )
    (comp (ref "R140")
      (value "18k")
      (footprint "RESC1608X55N")
      (description "Resistor - 1%")
      (fields
        (field (name "PART NUMBER") "R0603_18K_1%_0.1W_100PPM")
        (field (name "POWER") "0.1W")
        (field (name "AUTHOR") "CERN DEM JLC")
      )
      (libsource (lib "Resistors") (part "Resistor - 1%"))
    )
    (comp (ref "R141")
      (value "18k")
      (footprint "RESC1608X55N")
      (description "Resistor - 1%")
      (fields
        (field (name "PART NUMBER") "R0603_18K_1%_0.1W_100PPM")
        (field (name "POWER") "0.1W")
        (field (name "AUTHOR") "CERN DEM JLC")
      )
      (libsource (lib "Resistors") (part "Resistor - 1%"))
    )
    (comp (ref "R142")
      (value "330")
      (footprint "RESC1608X55N")
      (description "Resistor - 1%")
      (fields
        (field (name "PART NUMBER") "R0603_330R_1%_0.1W_100PPM")
        (field (name "POWER") "0.1W")
        (field (name "AUTHOR") "CERN DEM JLC")
      )
      (libsource (lib "Resistors") (part "Resistor - 1%"))
    )
    (comp (ref "R143")
      (value "1k5")
      (footprint "RESC1608X55N")
      (description "Resistor - 1%")
      (fields
        (field (name "PART NUMBER") "R0603_1K5_1%_0.1W_100PPM")
        (field (name "POWER") "0.1W")
        (field (name "AUTHOR") "CERN DEM JLC")
      )
      (libsource (lib "Resistors") (part "Resistor - 1%"))
    )
    (comp (ref "TP1")
      (value "Test Point")
      (footprint "TPS127")
      (fields (field (name "PART NUMBER") "SMD_PAD_1.27X1.27MM") (field (name "AUTHOR") "CERN DEM JLC"))
      (libsource (lib "Eletro-mechanical") (part "Test Point"))
    )
    (comp (ref "TP16")
      (value "Test Point")
      (footprint "TPS127")
      (fields (field (name "PART NUMBER") "SMD_PAD_1.27X1.27MM") (field (name "AUTHOR") "CERN DEM JLC"))
      (libsource (lib "Eletro-mechanical") (part "Test Point"))
    )
  )
  (nets
    (net (code "1") (name "/P1V25_REF") (class "Default")
      (node (ref "IC16") (pin "4") (pinfunction "IN-_4") (pintype "input"))
      (node (ref "IC16") (pin "6") (pinfunction "IN-_6") (pintype "input"))
      (node (ref "IC16") (pin "8") (pinfunction "IN-_8") (pintype "input"))
      (node (ref "IC17") (pin "1") (pinfunction "Adj_1") (pintype "passive"))
      (node (ref "IC17") (pin "2") (pinfunction "C_2") (pintype "passive"))
      (node (ref "IC25") (pin "11") (pinfunction "IN+_11") (pintype "input"))
      (node (ref "R100") (pin "1") (pinfunction "1_1") (pintype "passive"))
      (node (ref "R93") (pin "2") (pinfunction "2_2") (pintype "passive"))
    )
    (net (code "2") (name "/PGOOD") (class "Default")
      (node (ref "D15") (pin "2") (pinfunction "A_2") (pintype "passive"))
      (node (ref "IC16") (pin "1") (pinfunction "OUT_1") (pintype "output"))
      (node (ref "IC16") (pin "13") (pinfunction "OUT_13") (pintype "output"))
      (node (ref "IC16") (pin "14") (pinfunction "OUT_14") (pintype "output"))
      (node (ref "IC16") (pin "2") (pinfunction "OUT_2") (pintype "output"))
      (node (ref "R92") (pin "2") (pinfunction "2_2") (pintype "passive"))
      (node (ref "TP16") (pin "1") (pinfunction "1_1") (pintype "bidirectional"))
    )
    (net (code "3") (name "/PGOOD_N7V5") (class "Default")
      (node (ref "IC5") (pin "8") (pinfunction "PGOOD_8") (pintype "output"))
      (node (ref "R25") (pin "2") (pinfunction "2_2") (pintype "passive"))
      (node (ref "TP1") (pin "1") (pinfunction "1_1") (pintype "bidirectional"))
    )
    (net (code "4") (name "/Vin_reg_n7") (class "Default")
      (node (ref "C35") (pin "2") (pinfunction "2_2") (pintype "passive"))
      (node (ref "IC5") (pin "11") (pinfunction "Vin_reg_11") (pintype "passive"))
      (node (ref "IC5") (pin "17") (pinfunction "INTVcc_17") (pintype "power_in"))
    )
    (net (code "5") (name "GND") (class "Default")
      (node (ref "C122") (pin "1") (pinfunction "1_1") (pintype "passive"))
      (node (ref "C139") (pin "2") (pinfunction "2_2") (pintype "passive"))
      (node (ref "C21") (pin "1") (pinfunction "1_1") (pintype "passive"))
      (node (ref "C22") (pin "1") (pinfunction "1_1") (pintype "passive"))
      (node (ref "C24") (pin "1") (pinfunction "1_1") (pintype "passive"))
      (node (ref "C25") (pin "1") (pinfunction "1_1") (pintype "passive"))
      (node (ref "C29") (pin "1") (pinfunction "1_1") (pintype "passive"))
      (node (ref "C30") (pin "1") (pinfunction "1_1") (pintype "passive"))
      (node (ref "C31") (pin "1") (pinfunction "1_1") (pintype "passive"))
      (node (ref "C40") (pin "1") (pinfunction "1_1") (pintype "passive"))
      (node (ref "C43") (pin "2") (pinfunction "2_2") (pintype "passive"))
      (node (ref "C50") (pin "1") (pinfunction "1_1") (pintype "passive"))
      (node (ref "C51") (pin "1") (pinfunction "1_1") (pintype "passive"))
      (node (ref "C54") (pin "2") (pinfunction "2_2") (pintype "passive"))
      (node (ref "C55") (pin "1") (pinfunction "1_1") (pintype "passive"))
      (node (ref "C56") (pin "1") (pinfunction "1_1") (pintype "passive"))
      (node (ref "C57") (pin "1") (pinfunction "1_1") (pintype "passive"))
      (node (ref "C58") (pin "1") (pinfunction "1_1") (pintype "passive"))
      (node (ref "C61") (pin "2") (pinfunction "2_2") (pintype "passive"))
      (node (ref "C63") (pin "1") (pinfunction "1_1") (pintype "passive"))
      (node (ref "C64") (pin "1") (pinfunction "1_1") (pintype "passive"))
      (node (ref "C66") (pin "1") (pinfunction "1_1") (pintype "passive"))
      (node (ref "C68") (pin "1") (pinfunction "1_1") (pintype "passive"))
      (node (ref "C69") (pin "1") (pinfunction "1_1") (pintype "passive"))
      (node (ref "C70") (pin "1") (pinfunction "1_1") (pintype "passive"))
      (node (ref "C74") (pin "1") (pinfunction "1_1") (pintype "passive"))
      (node (ref "C75") (pin "1") (pinfunction "1_1") (pintype "passive"))
      (node (ref "C76") (pin "1") (pinfunction "1_1") (pintype "passive"))
      (node (ref "FL1") (pin "4") (pinfunction "CG_4") (pintype "passive"))
      (node (ref "FL2") (pin "4") (pinfunction "CG_4") (pintype "passive"))
      (node (ref "IC12") (pin "1") (pinfunction "PGND_1") (pintype "power_in"))
      (node (ref "IC12") (pin "11") (pinfunction "EP_11") (pintype "power_in"))
      (node (ref "IC12") (pin "4") (pinfunction "NC_4") (pintype "passive"))
      (node (ref "IC12") (pin "6") (pinfunction "AGND_6") (pintype "power_in"))
      (node (ref "IC16") (pin "11") (pinfunction "IN+_11") (pintype "input"))
      (node (ref "IC16") (pin "12") (pinfunction "GND_12") (pintype "power_in"))
      (node (ref "IC17") (pin "3") (pinfunction "A_3") (pintype "passive"))
      (node (ref "IC19") (pin "4") (pinfunction "GND_4") (pintype "power_in"))
      (node (ref "IC19") (pin "8") (pinfunction "EP_8") (pintype "power_in"))
      (node (ref "IC20") (pin "1") (pinfunction "GND_1") (pintype "power_in"))
      (node (ref "IC25") (pin "12") (pinfunction "GND_12") (pintype "power_in"))
      (node (ref "IC25") (pin "4") (pinfunction "IN-_4") (pintype "input"))
      (node (ref "IC25") (pin "5") (pinfunction "IN+_5") (pintype "input"))
      (node (ref "IC25") (pin "6") (pinfunction "IN-_6") (pintype "input"))
      (node (ref "IC25") (pin "7") (pinfunction "IN+_7") (pintype "input"))
      (node (ref "IC25") (pin "8") (pinfunction "IN-_8") (pintype "input"))
      (node (ref "IC25") (pin "9") (pinfunction "IN+_9") (pintype "input"))
      (node (ref "IC4") (pin "3") (pinfunction "GND_3") (pintype "power_in"))
      (node (ref "IC4") (pin "6") (pinfunction "GND_6") (pintype "power_in"))
      (node (ref "IC4") (pin "9") (pinfunction "EP_9") (pintype "power_in"))
      (node (ref "IC5") (pin "13") (pinfunction "Vout_sns_13") (pintype "passive"))
      (node (ref "IC5") (pin "16") (pinfunction "EXTVcc_16") (pintype "power_in"))
      (node (ref "IC5") (pin "6") (pinfunction "GND_6") (pintype "power_in"))
      (node (ref "IC8") (pin "11") (pinfunction "GND_11") (pintype "power_in"))
      (node (ref "IC8") (pin "8") (pinfunction "GND_8") (pintype "power_in"))
      (node (ref "L3") (pin "2") (pinfunction "2_2") (pintype "passive"))
      (node (ref "LD16") (pin "1") (pinfunction "C_1") (pintype "passive"))
      (node (ref "LD17") (pin "1") (pinfunction "C_1") (pintype "passive"))
      (node (ref "LD18") (pin "2") (pinfunction "A_2") (pintype "passive"))
      (node (ref "LD19") (pin "1") (pinfunction "C_1") (pintype "passive"))
      (node (ref "LD3") (pin "1") (pinfunction "C_1") (pintype "passive"))
      (node (ref "LD5") (pin "1") (pinfunction "C_1") (pintype "passive"))
      (node (ref "R118") (pin "2") (pinfunction "2_2") (pintype "passive"))
      (node (ref "R125") (pin "2") (pinfunction "2_2") (pintype "passive"))
      (node (ref "R143") (pin "1") (pinfunction "1_1") (pintype "passive"))
      (node (ref "R16") (pin "1") (pinfunction "1_1") (pintype "passive"))
      (node (ref "R18") (pin "1") (pinfunction "1_1") (pintype "passive"))
      (node (ref "R31") (pin "1") (pinfunction "1_1") (pintype "passive"))
      (node (ref "R47") (pin "2") (pinfunction "2_2") (pintype "passive"))
      (node (ref "R48") (pin "1") (pinfunction "1_1") (pintype "passive"))
      (node (ref "R54") (pin "1") (pinfunction "1_1") (pintype "passive"))
      (node (ref "R82") (pin "1") (pinfunction "1_1") (pintype "passive"))
      (node (ref "R86") (pin "1") (pinfunction "1_1") (pintype "passive"))
      (node (ref "R95") (pin "2") (pinfunction "2_2") (pintype "passive"))
      (node (ref "R97") (pin "1") (pinfunction "1_1") (pintype "passive"))
      (node (ref "R99") (pin "1") (pinfunction "1_1") (pintype "passive"))
    )
    (net (code "6") (name "N8V0") (class "Default")
      (node (ref "C31") (pin "2") (pinfunction "2_2") (pintype "passive"))
      (node (ref "L4") (pin "2") (pinfunction "2_2") (pintype "passive"))
      (node (ref "R108") (pin "1") (pinfunction "1_1") (pintype "passive"))
      (node (ref "R91") (pin "2") (pinfunction "2_2") (pintype "passive"))
    )
    (net (code "7") (name "N8V0R") (class "Default")
      (node (ref "C26") (pin "1") (pinfunction "1_1") (pintype "passive"))
      (node (ref "C27") (pin "1") (pinfunction "1_1") (pintype "passive"))
      (node (ref "C29") (pin "2") (pinfunction "2_2") (pintype "passive"))
      (node (ref "C30") (pin "2") (pinfunction "2_2") (pintype "passive"))
      (node (ref "C35") (pin "1") (pinfunction "1_1") (pintype "passive"))
      (node (ref "C59") (pin "2") (pinfunction "2_2") (pintype "passive"))
      (node (ref "C62") (pin "1") (pinfunction "1_1") (pintype "passive"))
      (node (ref "C74") (pin "2") (pinfunction "2_2") (pintype "passive"))
      (node (ref "C75") (pin "2") (pinfunction "2_2") (pintype "passive"))
      (node (ref "C76") (pin "2") (pinfunction "2_2") (pintype "passive"))
      (node (ref "IC5") (pin "1") (pinfunction "Vout-_1") (pintype "power_in"))
      (node (ref "IC5") (pin "10") (pinfunction "SVout-_10") (pintype "power_in"))
      (node (ref "IC5") (pin "2") (pinfunction "Vout-_2") (pintype "power_in"))
      (node (ref "IC5") (pin "26") (pinfunction "Vout-_26") (pintype "power_in"))
      (node (ref "IC5") (pin "27") (pinfunction "Vout-_27") (pintype "power_in"))
      (node (ref "IC5") (pin "28") (pinfunction "Vout-_28") (pintype "power_in"))
      (node (ref "IC5") (pin "29") (pinfunction "SVout-_29") (pintype "power_in"))
      (node (ref "L4") (pin "1") (pinfunction "1_1") (pintype "passive"))
      (node (ref "R19") (pin "1") (pinfunction "1_1") (pintype "passive"))
      (node (ref "R20") (pin "1") (pinfunction "1_1") (pintype "passive"))
      (node (ref "R33") (pin "1") (pinfunction "1_1") (pintype "passive"))
    )
    (net (code "8") (name "Net-(C23-Pad2)") (class "Default")
      (node (ref "C23") (pin "2") (pinfunction "2_2") (pintype "passive"))
      (node (ref "IC5") (pin "19") (pinfunction "SW_19") (pintype "power_in"))
      (node (ref "IC5") (pin "20") (pinfunction "SW_20") (pintype "power_in"))
      (node (ref "IC5") (pin "21") (pinfunction "SW_21") (pintype "power_in"))
      (node (ref "IC5") (pin "22") (pinfunction "SW_22") (pintype "power_in"))
      (node (ref "IC5") (pin "23") (pinfunction "SW_23") (pintype "power_in"))
      (node (ref "IC5") (pin "24") (pinfunction "SW_24") (pintype "power_in"))
      (node (ref "IC5") (pin "25") (pinfunction "SW_25") (pintype "power_in"))
      (node (ref "L3") (pin "1") (pinfunction "1_1") (pintype "passive"))
    )
    (net (code "9") (name "Net-(C27-Pad2)") (class "Default")
      (node (ref "C27") (pin "2") (pinfunction "2_2") (pintype "passive"))
      (node (ref "R15") (pin "1") (pinfunction "1_1") (pintype "passive"))
    )
    (net (code "10") (name "Net-(D3-C)") (class "Default")
      (node (ref "C21") (pin "2") (pinfunction "2_2") (pintype "passive"))
      (node (ref "C54") (pin "1") (pinfunction "1_1") (pintype "passive"))
      (node (ref "C61") (pin "1") (pinfunction "1_1") (pintype "passive"))
      (node (ref "D3") (pin "1") (pinfunction "C_1") (pintype "passive"))
      (node (ref "IC4") (pin "5") (pinfunction "EN/UVLO_5") (pintype "input"))
      (node (ref "IC4") (pin "8") (pinfunction "VIN_8") (pintype "input"))
      (node (ref "L1") (pin "1") (pinfunction "1_1") (pintype "passive"))
    )
    (net (code "11") (name "Net-(D15-C)") (class "Default")
      (node (ref "D15") (pin "1") (pinfunction "C_1") (pintype "passive"))
      (node (ref "IC25") (pin "13") (pinfunction "OUT_13") (pintype "output"))
      (node (ref "LD6") (pin "1") (pinfunction "C_1") (pintype "passive"))
    )
    (net (code "12") (name "Net-(FL1-B)") (class "Default")
      (node (ref "FL1") (pin "1") (pinfunction "B_1") (pintype "passive"))
      (node (ref "J3") (pin "1") (pinfunction "1_1") (pintype "bidirectional"))
    )
    (net (code "13") (name "Net-(FL1-PSG)") (class "Default")
      (node (ref "FL1") (pin "3") (pinfunction "PSG_3") (pintype "passive"))
      (node (ref "J3") (pin "2") (pinfunction "2_2") (pintype "bidirectional"))
    )
    (net (code "14") (name "Net-(FL2-B)") (class "Default")
      (node (ref "FL2") (pin "1") (pinfunction "B_1") (pintype "passive"))
      (node (ref "J3") (pin "3") (pinfunction "3_3") (pintype "bidirectional"))
    )
    (net (code "15") (name "Net-(FL2-PSG)") (class "Default")
      (node (ref "FL2") (pin "3") (pinfunction "PSG_3") (pintype "passive"))
      (node (ref "J3") (pin "4") (pinfunction "4_4") (pintype "bidirectional"))
    )
    (net (code "16") (name "Net-(IC5-BOOST)") (class "Default")
      (node (ref "C23") (pin "1") (pinfunction "1_1") (pintype "passive"))
      (node (ref "IC5") (pin "18") (pinfunction "BOOST_18") (pintype "passive"))
    )
    (net (code "17") (name "Net-(IC5-ITH)") (class "Default")
      (node (ref "C26") (pin "2") (pinfunction "2_2") (pintype "passive"))
      (node (ref "IC5") (pin "15") (pinfunction "ITH_15") (pintype "passive"))
      (node (ref "R15") (pin "2") (pinfunction "2_2") (pintype "passive"))
    )
    (net (code "18") (name "Net-(IC5-Iset)") (class "Default")
      (node (ref "C62") (pin "2") (pinfunction "2_2") (pintype "passive"))
      (node (ref "IC5") (pin "14") (pinfunction "Iset_14") (pintype "passive"))
      (node (ref "R20") (pin "2") (pinfunction "2_2") (pintype "passive"))
    )
    (net (code "19") (name "Net-(IC5-MODE{slash}SYNC)") (class "Default")
      (node (ref "IC5") (pin "7") (pinfunction "MODE/SYNC_7") (pintype "input"))
      (node (ref "R18") (pin "2") (pinfunction "2_2") (pintype "passive"))
    )
    (net (code "20") (name "Net-(IC5-PGDFB)") (class "Default")
      (node (ref "IC5") (pin "9") (pinfunction "PGDFB_9") (pintype "input"))
      (node (ref "R16") (pin "2") (pinfunction "2_2") (pintype "passive"))
      (node (ref "R33") (pin "2") (pinfunction "2_2") (pintype "passive"))
    )
    (net (code "21") (name "Net-(IC5-RUN)") (class "Default")
      (node (ref "IC5") (pin "5") (pinfunction "RUN_5") (pintype "input"))
      (node (ref "R14") (pin "1") (pinfunction "1_1") (pintype "passive"))
    )
    (net (code "22") (name "Net-(IC5-Rt)") (class "Default")
      (node (ref "IC5") (pin "12") (pinfunction "Rt_12") (pintype "input"))
      (node (ref "R19") (pin "2") (pinfunction "2_2") (pintype "passive"))
    )
    (net (code "23") (name "Net-(IC8-ILIM)") (class "Default")
      (node (ref "IC8") (pin "5") (pinfunction "ILIM_5") (pintype "input"))
      (node (ref "R48") (pin "2") (pinfunction "2_2") (pintype "passive"))
    )
    (net (code "24") (name "Net-(IC8-PGFB)") (class "Default")
      (node (ref "IC8") (pin "6") (pinfunction "PGFB_6") (pintype "input"))
      (node (ref "R86") (pin "2") (pinfunction "2_2") (pintype "passive"))
      (node (ref "R87") (pin "1") (pinfunction "1_1") (pintype "passive"))
    )
    (net (code "25") (name "Net-(IC8-SET)") (class "Default")
      (node (ref "C43") (pin "1") (pinfunction "1_1") (pintype "passive"))
      (node (ref "IC8") (pin "7") (pinfunction "SET_7") (pintype "input"))
      (node (ref "R54") (pin "2") (pinfunction "2_2") (pintype "passive"))
    )
    (net (code "26") (name "Net-(IC12-EN)") (class "Default")
      (node (ref "C50") (pin "2") (pinfunction "2_2") (pintype "passive"))
      (node (ref "C57") (pin "2") (pinfunction "2_2") (pintype "passive"))
      (node (ref "C58") (pin "2") (pinfunction "2_2") (pintype "passive"))
      (node (ref "IC12") (pin "2") (pinfunction "VIN_2") (pintype "input"))
      (node (ref "IC12") (pin "3") (pinfunction "EN_3") (pintype "input"))
      (node (ref "IC20") (pin "3") (pinfunction "VIN_3") (pintype "input"))
      (node (ref "IC20") (pin "5") (pinfunction "EN_5") (pintype "input"))
      (node (ref "L1") (pin "2") (pinfunction "2_2") (pintype "passive"))
    )
    (net (code "27") (name "Net-(IC12-FB)") (class "Default")
      (node (ref "IC12") (pin "5") (pinfunction "FB_5") (pintype "input"))
      (node (ref "R81") (pin "1") (pinfunction "1_1") (pintype "passive"))
      (node (ref "R82") (pin "2") (pinfunction "2_2") (pintype "passive"))
    )
    (net (code "28") (name "Net-(IC12-SW)") (class "Default")
      (node (ref "IC12") (pin "9") (pinfunction "SW_9") (pintype "output"))
      (node (ref "L2") (pin "1") (pinfunction "1_1") (pintype "passive"))
    )
    (net (code "29") (name "Net-(IC16A-IN+)") (class "Default")
      (node (ref "IC16") (pin "5") (pinfunction "IN+_5") (pintype "input"))
      (node (ref "R94") (pin "2") (pinfunction "2_2") (pintype "passive"))
      (node (ref "R95") (pin "1") (pinfunction "1_1") (pintype "passive"))
    )
    (net (code "30") (name "Net-(IC16B-IN+)") (class "Default")
      (node (ref "IC16") (pin "7") (pinfunction "IN+_7") (pintype "input"))
      (node (ref "R96") (pin "1") (pinfunction "1_1") (pintype "passive"))
      (node (ref "R97") (pin "2") (pinfunction "2_2") (pintype "passive"))
    )
    (net (code "31") (name "Net-(IC16C-IN+)") (class "Default")
      (node (ref "IC16") (pin "9") (pinfunction "IN+_9") (pintype "input"))
      (node (ref "R98") (pin "1") (pinfunction "1_1") (pintype "passive"))
      (node (ref "R99") (pin "2") (pinfunction "2_2") (pintype "passive"))
    )
    (net (code "32") (name "Net-(IC16D-IN-)") (class "Default")
      (node (ref "IC16") (pin "10") (pinfunction "IN-_10") (pintype "input"))
      (node (ref "R91") (pin "1") (pinfunction "1_1") (pintype "passive"))
      (node (ref "R93") (pin "1") (pinfunction "1_1") (pintype "passive"))
    )
    (net (code "33") (name "Net-(IC19-EN)") (class "Default")
      (node (ref "IC19") (pin "3") (pinfunction "EN_3") (pintype "input"))
      (node (ref "R118") (pin "1") (pinfunction "1_1") (pintype "passive"))
      (node (ref "R28") (pin "1") (pinfunction "1_1") (pintype "passive"))
    )
    (net (code "34") (name "Net-(IC19-FB)") (class "Default")
      (node (ref "C71") (pin "1") (pinfunction "1_1") (pintype "passive"))
      (node (ref "C72") (pin "1") (pinfunction "1_1") (pintype "passive"))
      (node (ref "IC19") (pin "6") (pinfunction "FB_6") (pintype "input"))
      (node (ref "R30") (pin "1") (pinfunction "1_1") (pintype "passive"))
      (node (ref "R31") (pin "2") (pinfunction "2_2") (pintype "passive"))
    )
    (net (code "35") (name "Net-(IC19-RON)") (class "Default")
      (node (ref "IC19") (pin "2") (pinfunction "RON_2") (pintype "input"))
      (node (ref "R27") (pin "1") (pinfunction "1_1") (pintype "passive"))
    )
    (net (code "36") (name "Net-(IC19-SS)") (class "Default")
      (node (ref "C70") (pin "2") (pinfunction "2_2") (pintype "passive"))
      (node (ref "IC19") (pin "5") (pinfunction "SS_5") (pintype "passive"))
    )
    (net (code "37") (name "Net-(IC20-BST)") (class "Default")
      (node (ref "C46") (pin "1") (pinfunction "1_1") (pintype "passive"))
      (node (ref "IC20") (pin "6") (pinfunction "BST_6") (pintype "input"))
    )
    (net (code "38") (name "Net-(IC20-FB)") (class "Default")
      (node (ref "IC20") (pin "4") (pinfunction "FB_4") (pintype "input"))
      (node (ref "R124") (pin "1") (pinfunction "1_1") (pintype "passive"))
      (node (ref "R125") (pin "1") (pinfunction "1_1") (pintype "passive"))
    )
    (net (code "39") (name "Net-(IC20-SW)") (class "Default")
      (node (ref "C46") (pin "2") (pinfunction "2_2") (pintype "passive"))
      (node (ref "IC20") (pin "2") (pinfunction "SW_2") (pintype "output"))
      (node (ref "L5") (pin "1") (pinfunction "1_1") (pintype "passive"))
    )
    (net (code "40") (name "Net-(IC25D-IN-)") (class "Default")
      (node (ref "IC25") (pin "10") (pinfunction "IN-_10") (pintype "input"))
      (node (ref "R141") (pin "1") (pinfunction "1_1") (pintype "passive"))
      (node (ref "R143") (pin "2") (pinfunction "2_2") (pintype "passive"))
    )
    (net (code "41") (name "Net-(LD3-A)") (class "Default")
      (node (ref "LD3") (pin "2") (pinfunction "A_2") (pintype "passive"))
      (node (ref "R21") (pin "2") (pinfunction "2_2") (pintype "passive"))
    )
    (net (code "42") (name "Net-(LD5-A)") (class "Default")
      (node (ref "LD5") (pin "2") (pinfunction "A_2") (pintype "passive"))
      (node (ref "R55") (pin "1") (pinfunction "1_1") (pintype "passive"))
    )
    (net (code "43") (name "Net-(LD6-A)") (class "Default")
      (node (ref "LD6") (pin "2") (pinfunction "A_2") (pintype "passive"))
      (node (ref "R142") (pin "1") (pinfunction "1_1") (pintype "passive"))
    )
    (net (code "44") (name "Net-(LD16-A)") (class "Default")
      (node (ref "LD16") (pin "2") (pinfunction "A_2") (pintype "passive"))
      (node (ref "R109") (pin "2") (pinfunction "2_2") (pintype "passive"))
    )
    (net (code "45") (name "Net-(LD17-A)") (class "Default")
      (node (ref "LD17") (pin "2") (pinfunction "A_2") (pintype "passive"))
      (node (ref "R110") (pin "1") (pinfunction "1_1") (pintype "passive"))
    )
    (net (code "46") (name "Net-(LD18-C)") (class "Default")
      (node (ref "LD18") (pin "1") (pinfunction "C_1") (pintype "passive"))
      (node (ref "R108") (pin "2") (pinfunction "2_2") (pintype "passive"))
    )
    (net (code "47") (name "Net-(LD19-A)") (class "Default")
      (node (ref "LD19") (pin "2") (pinfunction "A_2") (pintype "passive"))
      (node (ref "R111") (pin "1") (pinfunction "1_1") (pintype "passive"))
    )
    (net (code "48") (name "Net-(R26-Pad1)") (class "Default")
      (node (ref "R26") (pin "1") (pinfunction "1_1") (pintype "passive"))
      (node (ref "R27") (pin "2") (pinfunction "2_2") (pintype "passive"))
    )
    (net (code "49") (name "Net-(R140-Pad1)") (class "Default")
      (node (ref "R140") (pin "1") (pinfunction "1_1") (pintype "passive"))
      (node (ref "R141") (pin "2") (pinfunction "2_2") (pintype "passive"))
    )
    (net (code "50") (name "P3V3") (class "Default")
      (node (ref "C51") (pin "2") (pinfunction "2_2") (pintype "passive"))
      (node (ref "C55") (pin "2") (pinfunction "2_2") (pintype "passive"))
      (node (ref "C56") (pin "2") (pinfunction "2_2") (pintype "passive"))
      (node (ref "IC12") (pin "10") (pinfunction "VOS_10") (pintype "input"))
      (node (ref "IC12") (pin "8") (pinfunction "SLEEP_8") (pintype "input"))
      (node (ref "IC16") (pin "3") (pinfunction "V+_3") (pintype "power_in"))
      (node (ref "IC25") (pin "3") (pinfunction "V+_3") (pintype "power_in"))
      (node (ref "L2") (pin "2") (pinfunction "2_2") (pintype "passive"))
      (node (ref "L5") (pin "2") (pinfunction "2_2") (pintype "passive"))
      (node (ref "R100") (pin "2") (pinfunction "2_2") (pintype "passive"))
      (node (ref "R111") (pin "2") (pinfunction "2_2") (pintype "passive"))
      (node (ref "R124") (pin "2") (pinfunction "2_2") (pintype "passive"))
      (node (ref "R14") (pin "2") (pinfunction "2_2") (pintype "passive"))
      (node (ref "R142") (pin "2") (pinfunction "2_2") (pintype "passive"))
      (node (ref "R25") (pin "1") (pinfunction "1_1") (pintype "passive"))
      (node (ref "R81") (pin "2") (pinfunction "2_2") (pintype "passive"))
      (node (ref "R92") (pin "1") (pinfunction "1_1") (pintype "passive"))
      (node (ref "R94") (pin "1") (pinfunction "1_1") (pintype "passive"))
    )
    (net (code "51") (name "P5V0") (class "Default")
      (node (ref "C122") (pin "2") (pinfunction "2_2") (pintype "passive"))
      (node (ref "C139") (pin "1") (pinfunction "1_1") (pintype "passive"))
      (node (ref "C22") (pin "2") (pinfunction "2_2") (pintype "passive"))
      (node (ref "IC4") (pin "1") (pinfunction "VOUT_1") (pintype "power_in"))
      (node (ref "IC4") (pin "2") (pinfunction "SENS_2") (pintype "input"))
      (node (ref "IC8") (pin "1") (pinfunction "IN_1") (pintype "input"))
      (node (ref "IC8") (pin "2") (pinfunction "IN_2") (pintype "input"))
      (node (ref "IC8") (pin "3") (pinfunction "EN/UV_3") (pintype "input"))
      (node (ref "R21") (pin "1") (pinfunction "1_1") (pintype "passive"))
    )
    (net (code "52") (name "P6V5") (class "Default")
      (node (ref "C68") (pin "2") (pinfunction "2_2") (pintype "passive"))
      (node (ref "C69") (pin "2") (pinfunction "2_2") (pintype "passive"))
      (node (ref "C71") (pin "2") (pinfunction "2_2") (pintype "passive"))
      (node (ref "C72") (pin "2") (pinfunction "2_2") (pintype "passive"))
      (node (ref "D3") (pin "2") (pinfunction "A_2") (pintype "passive"))
      (node (ref "IC19") (pin "7") (pinfunction "VOUT_7") (pintype "power_in"))
      (node (ref "R109") (pin "1") (pinfunction "1_1") (pintype "passive"))
      (node (ref "R30") (pin "2") (pinfunction "2_2") (pintype "passive"))
      (node (ref "R98") (pin "2") (pinfunction "2_2") (pintype "passive"))
    )
    (net (code "53") (name "P12V0") (class "Default")
      (node (ref "C24") (pin "2") (pinfunction "2_2") (pintype "passive"))
      (node (ref "C25") (pin "2") (pinfunction "2_2") (pintype "passive"))
      (node (ref "C59") (pin "1") (pinfunction "1_1") (pintype "passive"))
      (node (ref "C64") (pin "2") (pinfunction "2_2") (pintype "passive"))
      (node (ref "C66") (pin "2") (pinfunction "2_2") (pintype "passive"))
      (node (ref "FL2") (pin "2") (pinfunction "CB_2") (pintype "passive"))
      (node (ref "IC19") (pin "1") (pinfunction "VIN_1") (pintype "input"))
      (node (ref "IC5") (pin "3") (pinfunction "Vin_3") (pintype "power_in"))
      (node (ref "IC5") (pin "4") (pinfunction "Vin_4") (pintype "power_in"))
      (node (ref "R26") (pin "2") (pinfunction "2_2") (pintype "passive"))
      (node (ref "R28") (pin "2") (pinfunction "2_2") (pintype "passive"))
    )
    (net (code "54") (name "P30V0") (class "Default")
      (node (ref "C63") (pin "2") (pinfunction "2_2") (pintype "passive"))
      (node (ref "FL1") (pin "2") (pinfunction "CB_2") (pintype "passive"))
      (node (ref "R110") (pin "2") (pinfunction "2_2") (pintype "passive"))
      (node (ref "R140") (pin "2") (pinfunction "2_2") (pintype "passive"))
      (node (ref "R96") (pin "2") (pinfunction "2_2") (pintype "passive"))
    )
    (net (code "55") (name "REF_P3V3") (class "Default")
      (node (ref "C40") (pin "2") (pinfunction "2_2") (pintype "passive"))
      (node (ref "IC8") (pin "10") (pinfunction "OUT_10") (pintype "output"))
      (node (ref "IC8") (pin "9") (pinfunction "OUTS_9") (pintype "output"))
      (node (ref "R47") (pin "1") (pinfunction "1_1") (pintype "passive"))
      (node (ref "R55") (pin "2") (pinfunction "2_2") (pintype "passive"))
      (node (ref "R87") (pin "2") (pinfunction "2_2") (pintype "passive"))
    )
    (net (code "56") (name "unconnected-(IC4-NC-Pad4)") (class "Default")
      (node (ref "IC4") (pin "4") (pinfunction "NC_4") (pintype "passive"))
    )
    (net (code "57") (name "unconnected-(IC4-PG-Pad7)") (class "Default")
      (node (ref "IC4") (pin "7") (pinfunction "PG_7") (pintype "output"))
    )
    (net (code "58") (name "unconnected-(IC8-PG-Pad4)") (class "Default")
      (node (ref "IC8") (pin "4") (pinfunction "PG_4") (pintype "output"))
    )
    (net (code "59") (name "unconnected-(IC12-PG-Pad7)") (class "Default")
      (node (ref "IC12") (pin "7") (pinfunction "PG_7") (pintype "output"))
    )
    (net (code "60") (name "unconnected-(IC25A-OUT-Pad2)") (class "Default")
      (node (ref "IC25") (pin "2") (pinfunction "OUT_2") (pintype "output"))
    )
    (net (code "61") (name "unconnected-(IC25B-OUT-Pad1)") (class "Default")
      (node (ref "IC25") (pin "1") (pinfunction "OUT_1") (pintype "output"))
    )
    (net (code "62") (name "unconnected-(IC25C-OUT-Pad14)") (class "Default")
      (node (ref "IC25") (pin "14") (pinfunction "OUT_14") (pintype "output"))
    )
  )
)
